# Base_IC.net
KiCad netlist of a schematic drawn in Altium Designer
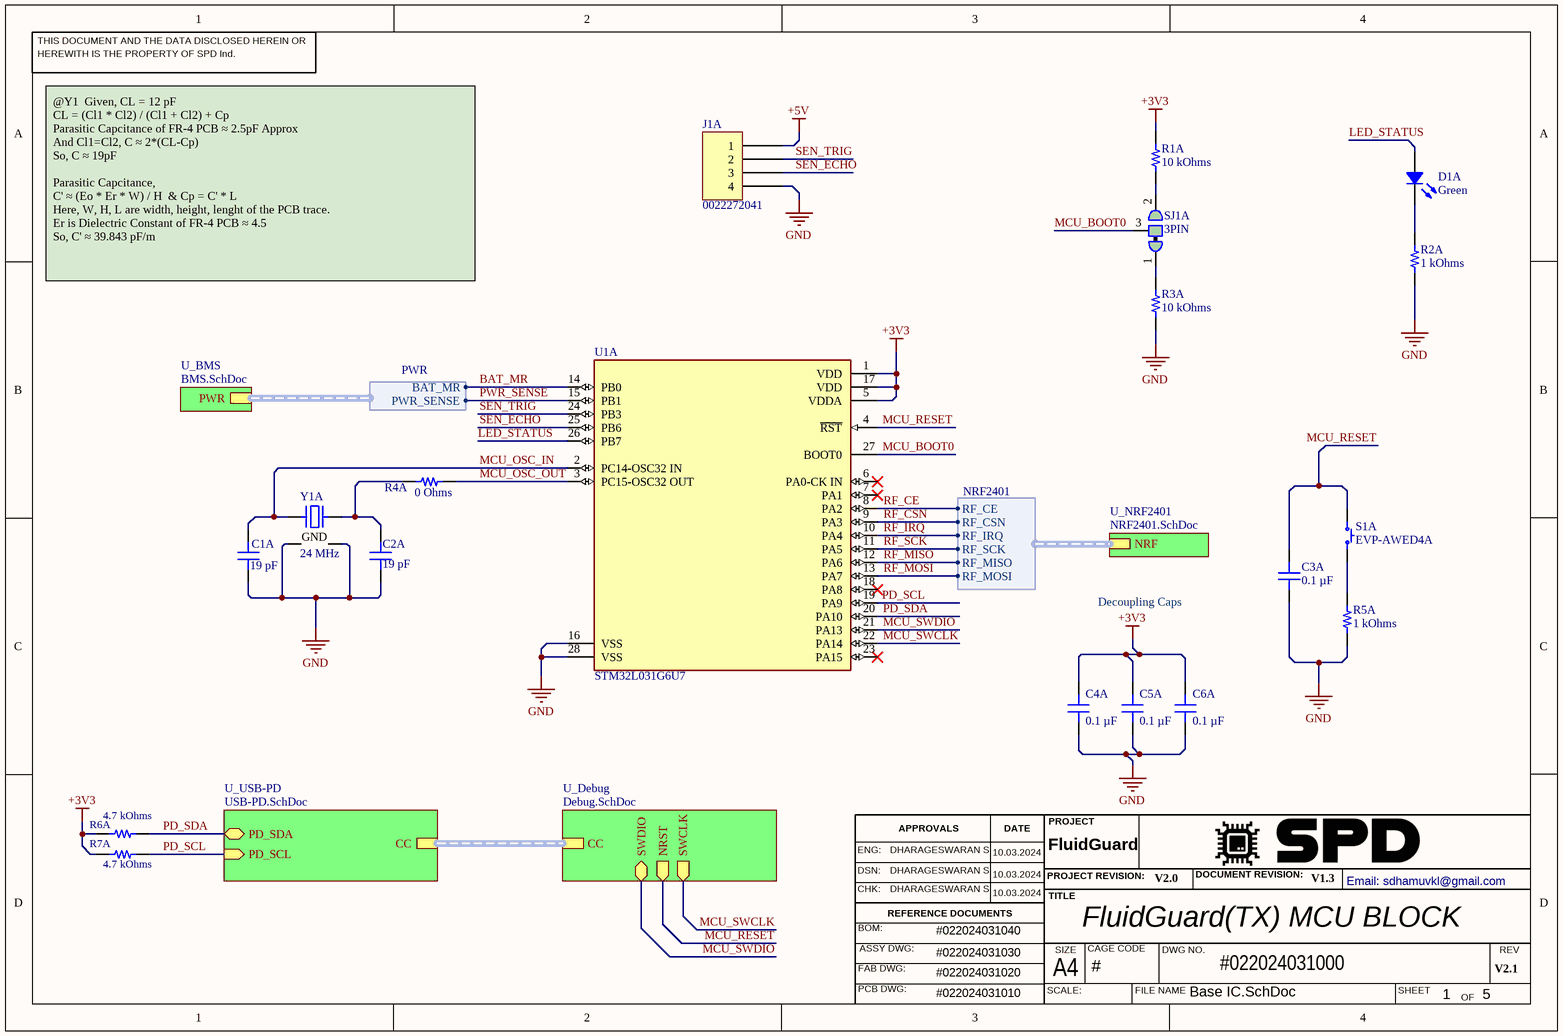
[diagram p0: Base IC.SchDoc]

(export (version "E")
  (design (tool "Eeschema 10.0.6"))
  (components
    (comp (ref "C1A")
      (value "19 pF")
      (footprint "CAP 0402_1005")
      (description "CAP CER 19PF 50VDC 0402 C0G 2%")
      (fields
        (field (name "PART NUMBER") "GJM1555C1H190GB01D")
        (field (name "MANUFACTURER") "Murata Electronics")
      )
      (libsource (lib "Postgres Altium Library - altium_library") (part "Capacitor"))
    )
    (comp (ref "C2A")
      (value "19 pF")
      (footprint "CAP 0402_1005")
      (description "CAP CER 19PF 50VDC 0402 C0G 2%")
      (fields
        (field (name "PART NUMBER") "GJM1555C1H190GB01D")
        (field (name "MANUFACTURER") "Murata Electronics")
      )
      (libsource (lib "Postgres Altium Library - altium_library") (part "Capacitor"))
    )
    (comp (ref "C3A")
      (value "0.1 µF")
      (footprint "CAP 0402_1005")
      (description "CAP CER 100NF 10V X7R 0402")
      (fields
        (field (name "PART NUMBER") "CL05B104KP5VPNC")
        (field (name "MANUFACTURER") "Samsung Electro-Mechanics")
      )
      (libsource (lib "Postgres Altium Library - altium_library") (part "Capacitor"))
    )
    (comp (ref "C4A")
      (value "0.1 µF")
      (footprint "CAP 0402_1005")
      (description "CAP CER 100NF 10V X7R 0402")
      (fields
        (field (name "PART NUMBER") "CL05B104KP5VPNC")
        (field (name "MANUFACTURER") "Samsung Electro-Mechanics")
      )
      (libsource (lib "Postgres Altium Library - altium_library") (part "Capacitor"))
    )
    (comp (ref "C5A")
      (value "0.1 µF")
      (footprint "CAP 0402_1005")
      (description "CAP CER 100NF 10V X7R 0402")
      (fields
        (field (name "PART NUMBER") "CL05B104KP5VPNC")
        (field (name "MANUFACTURER") "Samsung Electro-Mechanics")
      )
      (libsource (lib "Postgres Altium Library - altium_library") (part "Capacitor"))
    )
    (comp (ref "C6A")
      (value "0.1 µF")
      (footprint "CAP 0402_1005")
      (description "CAP CER 100NF 10V X7R 0402")
      (fields
        (field (name "PART NUMBER") "CL05B104KP5VPNC")
        (field (name "MANUFACTURER") "Samsung Electro-Mechanics")
      )
      (libsource (lib "Postgres Altium Library - altium_library") (part "Capacitor"))
    )
    (comp (ref "D1A")
      (value "Green")
      (footprint "LED 0402_1005 GREEN")
      (description "LED GREEN DIFFUSED 0402 SMD")
      (fields (field (name "PART NUMBER") "HSMG-C280") (field (name "MANUFACTURER") "Broadcom Limited"))
      (libsource (lib "Postgres Altium Library - altium_library") (part "LED"))
    )
    (comp (ref "J1A")
      (value "0022272041")
      (footprint "MOLEX KK 0022272041")
      (description "CONN HEADER VERT 4POS 2.54MM")
      (fields (field (name "MANUFACTURER") "Molex"))
      (libsource (lib "Postgres Altium Library - altium_library") (part "4 Pin"))
    )
    (comp (ref "R1A")
      (value "10 kOhms")
      (footprint "RES 0402_1005")
      (description "RES SMD 10K OHM 1% 1/16W 0402")
      (fields (field (name "PART NUMBER") "AA0402FR-0710KL") (field (name "TOLERANCE") "±1%"))
      (libsource (lib "Postgres Altium Library - altium_library") (part "Resistor"))
    )
    (comp (ref "R2A")
      (value "1 kOhms")
      (footprint "RES 0402_1005")
      (description "RES SMD 1K OHM 1% 1/16W 0402")
      (fields (field (name "PART NUMBER") "AA0402FR-071KL") (field (name "TOLERANCE") "±1%"))
      (libsource (lib "Postgres Altium Library - altium_library") (part "Resistor"))
    )
    (comp (ref "R3A")
      (value "10 kOhms")
      (footprint "RES 0402_1005")
      (description "RES SMD 10K OHM 1% 1/16W 0402")
      (fields (field (name "PART NUMBER") "AA0402FR-0710KL") (field (name "TOLERANCE") "±1%"))
      (libsource (lib "Postgres Altium Library - altium_library") (part "Resistor"))
    )
    (comp (ref "R4A")
      (value "0 Ohms")
      (footprint "RES 0402_1005")
      (description "RES SMD 0 OHM JUMPER 1/16W 0402")
      (fields (field (name "PART NUMBER") "AC0402JR-070RL") (field (name "TOLERANCE") "Jumper"))
      (libsource (lib "Postgres Altium Library - altium_library") (part "Resistor"))
    )
    (comp (ref "R5A")
      (value "1 kOhms")
      (footprint "RES 0402_1005")
      (description "RES SMD 1K OHM 1% 1/16W 0402")
      (fields (field (name "PART NUMBER") "AA0402FR-071KL") (field (name "TOLERANCE") "±1%"))
      (libsource (lib "Postgres Altium Library - altium_library") (part "Resistor"))
    )
    (comp (ref "R6A")
      (value "4.7 kOhms")
      (footprint "RES 0402_1005")
      (description "RES SMD 4.7K OHM 1% 1/16W 0402")
      (fields (field (name "PART NUMBER") "AC0402FR-074K7L") (field (name "TOLERANCE") "±1%"))
      (libsource (lib "Postgres Altium Library - altium_library") (part "Resistor"))
    )
    (comp (ref "R7A")
      (value "4.7 kOhms")
      (footprint "RES 0402_1005")
      (description "RES SMD 4.7K OHM 1% 1/16W 0402")
      (fields (field (name "PART NUMBER") "AC0402FR-074K7L") (field (name "TOLERANCE") "±1%"))
      (libsource (lib "Postgres Altium Library - altium_library") (part "Resistor"))
    )
    (comp (ref "S1A")
      (value "EVP-AWED4A")
      (footprint "PANASONIC EVPAW")
      (description "3.0MM X 2.0MM / 3.3N / 0.15MM ST")
      (fields (field (name "MANUFACTURER") "Panasonic Electronic Components"))
      (libsource (lib "Postgres Altium Library - altium_library") (part "SPST-NO 2 PIN"))
    )
    (comp (ref "SJ1A")
      (value "3PIN")
      (footprint "Rounded Jumper Joint 3-pin")
      (libsource (lib "Jumper-SMD") (part "Rounded Jumper Joint 3-pin"))
    )
    (comp (ref "U1A")
      (value "STM32L031G6U7")
      (footprint "FP-UFQFPN28-A0B0-MFG")
      (description "IC MCU 32BIT 32KB FLASH 28UFQFPN")
      (libsource (lib "STM32L031G6U7") (part "CMP-12105-000084-1"))
    )
    (comp (ref "Y1A")
      (value "24 MHz")
      (footprint "EPSON TSX-3225")
      (description "CRYSTAL 24.0000MHZ 9PF SMD")
      (fields (field (name "PART NUMBER") "TSX-3225 24.0000MF15X-AC3") (field (name "MANUFACTURER") "EPSON"))
      (libsource (lib "Postgres Altium Library - altium_library") (part "Epson Crystal TSX-3225"))
    )
  )
  (nets
    (net (code "3") (name "+3V3") (class "Default")
      (node (ref "C4A") (pin "2") (pinfunction "2_2") (pintype "passive"))
      (node (ref "C5A") (pin "2") (pinfunction "2_2") (pintype "passive"))
      (node (ref "C6A") (pin "2") (pinfunction "2_2") (pintype "passive"))
      (node (ref "R1A") (pin "2") (pinfunction "2_2") (pintype "passive"))
      (node (ref "R6A") (pin "2") (pinfunction "2_2") (pintype "passive"))
      (node (ref "R7A") (pin "2") (pinfunction "2_2") (pintype "passive"))
      (node (ref "U1A") (pin "1") (pinfunction "VDD_1") (pintype "power_in"))
      (node (ref "U1A") (pin "17") (pinfunction "VDD_17") (pintype "power_in"))
      (node (ref "U1A") (pin "5") (pinfunction "VDDA_5") (pintype "power_in"))
    )
    (net (code "4") (name "+5V") (class "Default")
      (node (ref "J1A") (pin "1") (pinfunction "1_1") (pintype "passive"))
    )
    (net (code "5") (name "/BAT_MR") (class "Default")
      (node (ref "U1A") (pin "14") (pinfunction "PB0_14") (pintype "bidirectional"))
    )
    (net (code "7") (name "/LED_STATUS") (class "Default")
      (node (ref "D1A") (pin "1") (pinfunction "1_1") (pintype "passive"))
      (node (ref "U1A") (pin "26") (pinfunction "PB7_26") (pintype "bidirectional"))
    )
    (net (code "8") (name "/MCU_BOOT0") (class "Default")
      (node (ref "SJ1A") (pin "3") (pinfunction "3_3") (pintype "passive"))
      (node (ref "U1A") (pin "27") (pinfunction "BOOT0_27") (pintype "passive"))
    )
    (net (code "9") (name "/MCU_OSC_IN") (class "Default")
      (node (ref "C1A") (pin "2") (pinfunction "2_2") (pintype "passive"))
      (node (ref "U1A") (pin "2") (pinfunction "PC14-OSC32_IN_2") (pintype "bidirectional"))
      (node (ref "Y1A") (pin "1") (pinfunction "1_1") (pintype "passive"))
    )
    (net (code "10") (name "/MCU_OSC_OUT") (class "Default")
      (node (ref "R4A") (pin "2") (pinfunction "2_2") (pintype "passive"))
      (node (ref "U1A") (pin "3") (pinfunction "PC15-OSC32_OUT_3") (pintype "bidirectional"))
    )
    (net (code "11") (name "/MCU_RESET") (class "Default")
      (node (ref "C3A") (pin "2") (pinfunction "2_2") (pintype "passive"))
      (node (ref "S1A") (pin "1") (pinfunction "1_1") (pintype "passive"))
      (node (ref "U1A") (pin "4") (pinfunction "~{RST}_4") (pintype "input"))
    )
    (net (code "12") (name "/MCU_SWCLK") (class "Default")
      (node (ref "U1A") (pin "22") (pinfunction "PA14_22") (pintype "bidirectional"))
    )
    (net (code "13") (name "/MCU_SWDIO") (class "Default")
      (node (ref "U1A") (pin "21") (pinfunction "PA13_21") (pintype "bidirectional"))
    )
    (net (code "14") (name "/PD_SCL") (class "Default")
      (node (ref "R7A") (pin "1") (pinfunction "1_1") (pintype "passive"))
      (node (ref "U1A") (pin "19") (pinfunction "PA9_19") (pintype "bidirectional"))
    )
    (net (code "15") (name "/PD_SDA") (class "Default")
      (node (ref "R6A") (pin "1") (pinfunction "1_1") (pintype "passive"))
      (node (ref "U1A") (pin "20") (pinfunction "PA10_20") (pintype "bidirectional"))
    )
    (net (code "16") (name "/PWR_SENSE") (class "Default")
      (node (ref "U1A") (pin "15") (pinfunction "PB1_15") (pintype "bidirectional"))
    )
    (net (code "17") (name "/RF_CE") (class "Default")
      (node (ref "U1A") (pin "8") (pinfunction "PA2_8") (pintype "bidirectional"))
    )
    (net (code "18") (name "/RF_CSN") (class "Default")
      (node (ref "U1A") (pin "9") (pinfunction "PA3_9") (pintype "bidirectional"))
    )
    (net (code "19") (name "/RF_IRQ") (class "Default")
      (node (ref "U1A") (pin "10") (pinfunction "PA4_10") (pintype "bidirectional"))
    )
    (net (code "20") (name "/RF_MISO") (class "Default")
      (node (ref "U1A") (pin "12") (pinfunction "PA6_12") (pintype "bidirectional"))
    )
    (net (code "21") (name "/RF_MOSI") (class "Default")
      (node (ref "U1A") (pin "13") (pinfunction "PA7_13") (pintype "bidirectional"))
    )
    (net (code "22") (name "/RF_SCK") (class "Default")
      (node (ref "U1A") (pin "11") (pinfunction "PA5_11") (pintype "bidirectional"))
    )
    (net (code "23") (name "/SEN_ECHO") (class "Default")
      (node (ref "J1A") (pin "3") (pinfunction "3_3") (pintype "passive"))
      (node (ref "U1A") (pin "25") (pinfunction "PB6_25") (pintype "bidirectional"))
    )
    (net (code "24") (name "/SEN_TRIG") (class "Default")
      (node (ref "J1A") (pin "2") (pinfunction "2_2") (pintype "passive"))
      (node (ref "U1A") (pin "24") (pinfunction "PB3_24") (pintype "bidirectional"))
    )
    (net (code "27") (name "GND") (class "Default")
      (node (ref "C1A") (pin "1") (pinfunction "1_1") (pintype "passive"))
      (node (ref "C2A") (pin "1") (pinfunction "1_1") (pintype "passive"))
      (node (ref "C3A") (pin "1") (pinfunction "1_1") (pintype "passive"))
      (node (ref "C4A") (pin "1") (pinfunction "1_1") (pintype "passive"))
      (node (ref "C5A") (pin "1") (pinfunction "1_1") (pintype "passive"))
      (node (ref "C6A") (pin "1") (pinfunction "1_1") (pintype "passive"))
      (node (ref "J1A") (pin "4") (pinfunction "4_4") (pintype "passive"))
      (node (ref "R2A") (pin "1") (pinfunction "1_1") (pintype "passive"))
      (node (ref "R3A") (pin "1") (pinfunction "1_1") (pintype "passive"))
      (node (ref "R5A") (pin "1") (pinfunction "1_1") (pintype "passive"))
      (node (ref "U1A") (pin "16") (pinfunction "VSS_16") (pintype "power_in"))
      (node (ref "U1A") (pin "28") (pinfunction "VSS_28") (pintype "power_in"))
      (node (ref "Y1A") (pin "2") (pinfunction "GND_2") (pintype "passive"))
      (node (ref "Y1A") (pin "4") (pinfunction "GND_4") (pintype "passive"))
    )
    (net (code "28") (name "Net-(C2A-Pad2)") (class "Default")
      (node (ref "C2A") (pin "2") (pinfunction "2_2") (pintype "passive"))
      (node (ref "R4A") (pin "1") (pinfunction "1_1") (pintype "passive"))
      (node (ref "Y1A") (pin "3") (pinfunction "3_3") (pintype "passive"))
    )
    (net (code "29") (name "Net-(D1A-Pad2)") (class "Default")
      (node (ref "D1A") (pin "2") (pinfunction "2_2") (pintype "passive"))
      (node (ref "R2A") (pin "2") (pinfunction "2_2") (pintype "passive"))
    )
    (net (code "30") (name "Net-(R1A-Pad1)") (class "Default")
      (node (ref "R1A") (pin "1") (pinfunction "1_1") (pintype "passive"))
      (node (ref "SJ1A") (pin "2") (pinfunction "2_2") (pintype "passive"))
    )
    (net (code "31") (name "Net-(R3A-Pad2)") (class "Default")
      (node (ref "R3A") (pin "2") (pinfunction "2_2") (pintype "passive"))
      (node (ref "SJ1A") (pin "1") (pinfunction "1_1") (pintype "passive"))
    )
    (net (code "32") (name "Net-(R5A-Pad2)") (class "Default")
      (node (ref "R5A") (pin "2") (pinfunction "2_2") (pintype "passive"))
      (node (ref "S1A") (pin "2") (pinfunction "2_2") (pintype "passive"))
    )
    (net (code "33") (name "unconnected-(U1A-PA0-CK_IN-Pad6)") (class "Default")
      (node (ref "U1A") (pin "6") (pinfunction "PA0-CK_IN_6") (pintype "bidirectional+no_connect"))
    )
    (net (code "34") (name "unconnected-(U1A-PA1-Pad7)") (class "Default")
      (node (ref "U1A") (pin "7") (pinfunction "PA1_7") (pintype "bidirectional+no_connect"))
    )
    (net (code "35") (name "unconnected-(U1A-PA8-Pad18)") (class "Default")
      (node (ref "U1A") (pin "18") (pinfunction "PA8_18") (pintype "bidirectional+no_connect"))
    )
    (net (code "36") (name "unconnected-(U1A-PA15-Pad23)") (class "Default")
      (node (ref "U1A") (pin "23") (pinfunction "PA15_23") (pintype "bidirectional+no_connect"))
    )
  )
)
